# soundMeter.net
KiCad netlist of a schematic drawn in EAGLE
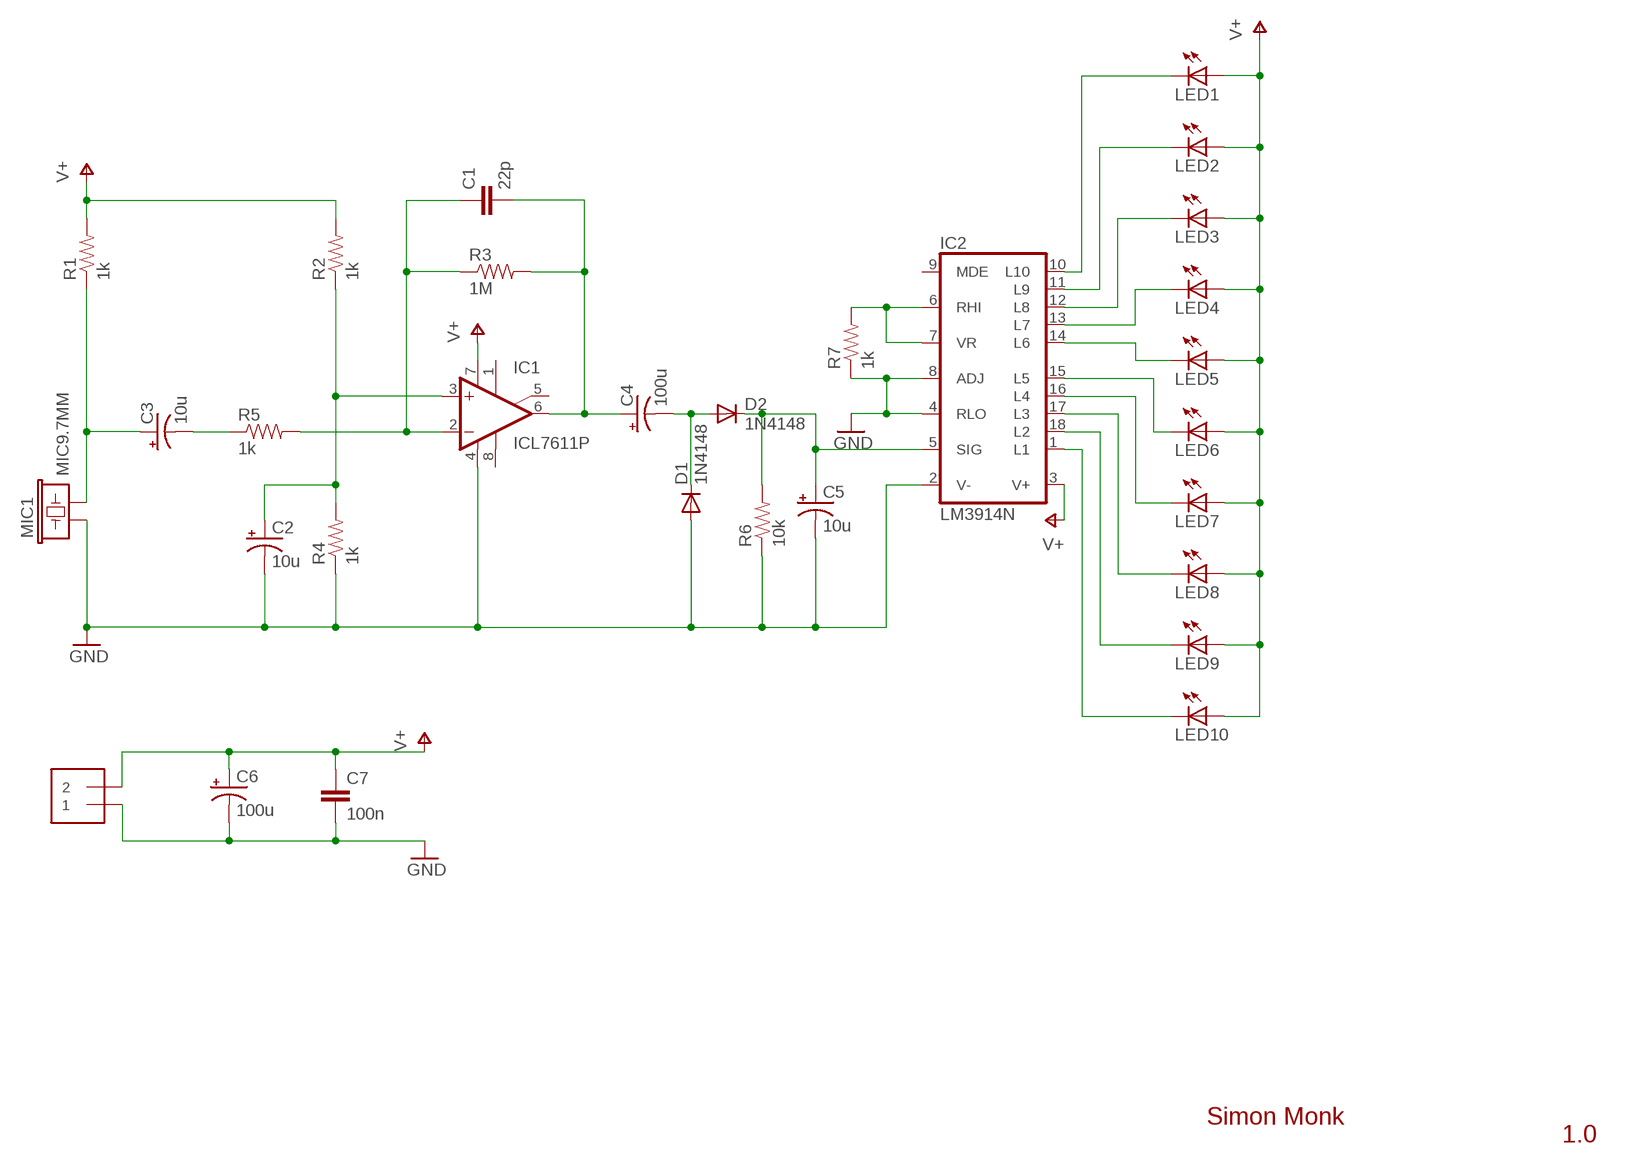
[diagram p0: schematic, sheet 1]

(export (version "E")
  (design (tool "Eeschema 10.0.6"))
  (components
    (comp (ref "C1")
      (value "22p")
      (footprint "eagle-import:CAP-PTH-SMALL")
      (libsource (lib "eagle-import") (part "CAPPTH"))
    )
    (comp (ref "C2")
      (value "10u")
      (footprint "eagle-import:CPOL-RADIAL-10UF-25V")
      (libsource (lib "eagle-import") (part "CAP_POLPTH2"))
    )
    (comp (ref "C3")
      (value "10u")
      (footprint "eagle-import:CPOL-RADIAL-10UF-25V")
      (libsource (lib "eagle-import") (part "CAP_POLPTH2"))
    )
    (comp (ref "C4")
      (value "100u")
      (footprint "eagle-import:CPOL-RADIAL-10UF-25V")
      (libsource (lib "eagle-import") (part "CAP_POLPTH2"))
    )
    (comp (ref "C5")
      (value "10u")
      (footprint "eagle-import:CPOL-RADIAL-10UF-25V")
      (libsource (lib "eagle-import") (part "CAP_POLPTH2"))
    )
    (comp (ref "C6")
      (value "100u")
      (footprint "eagle-import:CPOL-RADIAL-10UF-25V")
      (libsource (lib "eagle-import") (part "CAP_POLPTH2"))
    )
    (comp (ref "C7")
      (value "100n")
      (footprint "eagle-import:CAP-PTH-SMALL")
      (libsource (lib "eagle-import") (part "CAPPTH"))
    )
    (comp (ref "D1")
      (value "1N4148")
      (footprint "eagle-import:DO35-7")
      (libsource (lib "eagle-import") (part "1N4148DO35-7"))
    )
    (comp (ref "D2")
      (value "1N4148")
      (footprint "eagle-import:DO35-7")
      (libsource (lib "eagle-import") (part "1N4148DO35-7"))
    )
    (comp (ref "IC1")
      (value "ICL7611P")
      (footprint "eagle-import:DIL08")
      (libsource (lib "eagle-import") (part "ICL7611P"))
    )
    (comp (ref "IC2")
      (value "LM3914N")
      (footprint "eagle-import:DIL18")
      (libsource (lib "eagle-import") (part "LM3914N"))
    )
    (comp (ref "J1")
      (value "1X2-3.5MM")
      (footprint "eagle-import:1X2-3.5MM")
      (libsource (lib "eagle-import") (part "1X2-3.5MM"))
    )
    (comp (ref "LED1")
      (value "LED3MM")
      (footprint "eagle-import:LED3MM")
      (libsource (lib "eagle-import") (part "LED3MM"))
    )
    (comp (ref "LED2")
      (value "LED3MM")
      (footprint "eagle-import:LED3MM")
      (libsource (lib "eagle-import") (part "LED3MM"))
    )
    (comp (ref "LED3")
      (value "LED3MM")
      (footprint "eagle-import:LED3MM")
      (libsource (lib "eagle-import") (part "LED3MM"))
    )
    (comp (ref "LED4")
      (value "LED3MM")
      (footprint "eagle-import:LED3MM")
      (libsource (lib "eagle-import") (part "LED3MM"))
    )
    (comp (ref "LED5")
      (value "LED3MM")
      (footprint "eagle-import:LED3MM")
      (libsource (lib "eagle-import") (part "LED3MM"))
    )
    (comp (ref "LED6")
      (value "LED3MM")
      (footprint "eagle-import:LED3MM")
      (libsource (lib "eagle-import") (part "LED3MM"))
    )
    (comp (ref "LED7")
      (value "LED3MM")
      (footprint "eagle-import:LED3MM")
      (libsource (lib "eagle-import") (part "LED3MM"))
    )
    (comp (ref "LED8")
      (value "LED3MM")
      (footprint "eagle-import:LED3MM")
      (libsource (lib "eagle-import") (part "LED3MM"))
    )
    (comp (ref "LED9")
      (value "LED3MM")
      (footprint "eagle-import:LED3MM")
      (libsource (lib "eagle-import") (part "LED3MM"))
    )
    (comp (ref "LED10")
      (value "LED3MM")
      (footprint "eagle-import:LED3MM")
      (libsource (lib "eagle-import") (part "LED3MM"))
    )
    (comp (ref "MIC1")
      (value "MIC9.7MM")
      (footprint "eagle-import:MIC-9.7MM")
      (libsource (lib "eagle-import") (part "MIC9.7MM"))
    )
    (comp (ref "R1")
      (value "1k")
      (footprint "eagle-import:AXIAL-0.4")
      (libsource (lib "eagle-import") (part "RESISTORPTH-1/4W"))
    )
    (comp (ref "R2")
      (value "1k")
      (footprint "eagle-import:AXIAL-0.4")
      (libsource (lib "eagle-import") (part "RESISTORPTH-1/4W"))
    )
    (comp (ref "R3")
      (value "1M")
      (footprint "eagle-import:AXIAL-0.4")
      (libsource (lib "eagle-import") (part "RESISTORPTH-1/4W"))
    )
    (comp (ref "R4")
      (value "1k")
      (footprint "eagle-import:AXIAL-0.4")
      (libsource (lib "eagle-import") (part "RESISTORPTH-1/4W"))
    )
    (comp (ref "R5")
      (value "1k")
      (footprint "eagle-import:AXIAL-0.4")
      (libsource (lib "eagle-import") (part "RESISTORPTH-1/4W"))
    )
    (comp (ref "R6")
      (value "10k")
      (footprint "eagle-import:AXIAL-0.4")
      (libsource (lib "eagle-import") (part "RESISTORPTH-1/4W"))
    )
    (comp (ref "R7")
      (value "1k")
      (footprint "eagle-import:AXIAL-0.4")
      (libsource (lib "eagle-import") (part "RESISTORPTH-1/4W"))
    )
  )
  (nets
    (net (code "1") (name "GND") (class "Default")
      (node (ref "C2") (pin "2") (pinfunction "-_2") (pintype "passive"))
      (node (ref "C5") (pin "2") (pinfunction "-_2") (pintype "passive"))
      (node (ref "C6") (pin "2") (pinfunction "-_2") (pintype "passive"))
      (node (ref "C7") (pin "2") (pinfunction "2_2") (pintype "passive"))
      (node (ref "D1") (pin "A") (pinfunction "A_A") (pintype "passive"))
      (node (ref "IC1") (pin "4") (pinfunction "V-_4") (pintype "power_in"))
      (node (ref "IC2") (pin "2") (pinfunction "V-_2") (pintype "power_in"))
      (node (ref "IC2") (pin "4") (pinfunction "RLO_4") (pintype "input"))
      (node (ref "IC2") (pin "8") (pinfunction "ADJ_8") (pintype "input"))
      (node (ref "J1") (pin "1") (pinfunction "1_1") (pintype "passive"))
      (node (ref "MIC1") (pin "1") (pinfunction "1_1") (pintype "passive"))
      (node (ref "R4") (pin "P$1") (pinfunction "1_P$1") (pintype "passive"))
      (node (ref "R6") (pin "P$1") (pinfunction "1_P$1") (pintype "passive"))
      (node (ref "R7") (pin "P$1") (pinfunction "1_P$1") (pintype "passive"))
    )
    (net (code "2") (name "Net-(C2-+)") (class "Default")
      (node (ref "C2") (pin "1") (pinfunction "+_1") (pintype "passive"))
      (node (ref "IC1") (pin "3") (pinfunction "+IN_3") (pintype "input"))
      (node (ref "R2") (pin "P$1") (pinfunction "1_P$1") (pintype "passive"))
      (node (ref "R4") (pin "P$2") (pinfunction "2_P$2") (pintype "passive"))
    )
    (net (code "3") (name "Net-(C3-+)") (class "Default")
      (node (ref "C3") (pin "1") (pinfunction "+_1") (pintype "passive"))
      (node (ref "MIC1") (pin "2") (pinfunction "2_2") (pintype "passive"))
      (node (ref "R1") (pin "P$1") (pinfunction "1_P$1") (pintype "passive"))
    )
    (net (code "4") (name "Net-(C3--)") (class "Default")
      (node (ref "C3") (pin "2") (pinfunction "-_2") (pintype "passive"))
      (node (ref "R5") (pin "P$1") (pinfunction "1_P$1") (pintype "passive"))
    )
    (net (code "5") (name "Net-(C4-+)") (class "Default")
      (node (ref "C1") (pin "2") (pinfunction "2_2") (pintype "passive"))
      (node (ref "C4") (pin "1") (pinfunction "+_1") (pintype "passive"))
      (node (ref "IC1") (pin "6") (pinfunction "OUT_6") (pintype "output"))
      (node (ref "R3") (pin "P$2") (pinfunction "2_P$2") (pintype "passive"))
    )
    (net (code "6") (name "Net-(C4--)") (class "Default")
      (node (ref "C4") (pin "2") (pinfunction "-_2") (pintype "passive"))
      (node (ref "D1") (pin "C") (pinfunction "C_C") (pintype "passive"))
      (node (ref "D2") (pin "A") (pinfunction "A_A") (pintype "passive"))
    )
    (net (code "7") (name "Net-(C5-+)") (class "Default")
      (node (ref "C5") (pin "1") (pinfunction "+_1") (pintype "passive"))
      (node (ref "D2") (pin "C") (pinfunction "C_C") (pintype "passive"))
      (node (ref "IC2") (pin "5") (pinfunction "SIG_5") (pintype "input"))
      (node (ref "R6") (pin "P$2") (pinfunction "2_P$2") (pintype "passive"))
    )
    (net (code "8") (name "Net-(IC1--IN)") (class "Default")
      (node (ref "C1") (pin "1") (pinfunction "1_1") (pintype "passive"))
      (node (ref "IC1") (pin "2") (pinfunction "-IN_2") (pintype "input"))
      (node (ref "R3") (pin "P$1") (pinfunction "1_P$1") (pintype "passive"))
      (node (ref "R5") (pin "P$2") (pinfunction "2_P$2") (pintype "passive"))
    )
    (net (code "9") (name "Net-(IC2-L1)") (class "Default")
      (node (ref "IC2") (pin "1") (pinfunction "L1_1") (pintype "output"))
      (node (ref "LED10") (pin "K") (pinfunction "C_K") (pintype "passive"))
    )
    (net (code "10") (name "Net-(IC2-L2)") (class "Default")
      (node (ref "IC2") (pin "18") (pinfunction "L2_18") (pintype "output"))
      (node (ref "LED9") (pin "K") (pinfunction "C_K") (pintype "passive"))
    )
    (net (code "11") (name "Net-(IC2-L3)") (class "Default")
      (node (ref "IC2") (pin "17") (pinfunction "L3_17") (pintype "output"))
      (node (ref "LED8") (pin "K") (pinfunction "C_K") (pintype "passive"))
    )
    (net (code "12") (name "Net-(IC2-L4)") (class "Default")
      (node (ref "IC2") (pin "16") (pinfunction "L4_16") (pintype "output"))
      (node (ref "LED7") (pin "K") (pinfunction "C_K") (pintype "passive"))
    )
    (net (code "13") (name "Net-(IC2-L5)") (class "Default")
      (node (ref "IC2") (pin "15") (pinfunction "L5_15") (pintype "output"))
      (node (ref "LED6") (pin "K") (pinfunction "C_K") (pintype "passive"))
    )
    (net (code "14") (name "Net-(IC2-L6)") (class "Default")
      (node (ref "IC2") (pin "14") (pinfunction "L6_14") (pintype "output"))
      (node (ref "LED5") (pin "K") (pinfunction "C_K") (pintype "passive"))
    )
    (net (code "15") (name "Net-(IC2-L7)") (class "Default")
      (node (ref "IC2") (pin "13") (pinfunction "L7_13") (pintype "output"))
      (node (ref "LED4") (pin "K") (pinfunction "C_K") (pintype "passive"))
    )
    (net (code "16") (name "Net-(IC2-L8)") (class "Default")
      (node (ref "IC2") (pin "12") (pinfunction "L8_12") (pintype "output"))
      (node (ref "LED3") (pin "K") (pinfunction "C_K") (pintype "passive"))
    )
    (net (code "17") (name "Net-(IC2-L9)") (class "Default")
      (node (ref "IC2") (pin "11") (pinfunction "L9_11") (pintype "output"))
      (node (ref "LED2") (pin "K") (pinfunction "C_K") (pintype "passive"))
    )
    (net (code "18") (name "Net-(IC2-L10)") (class "Default")
      (node (ref "IC2") (pin "10") (pinfunction "L10_10") (pintype "output"))
      (node (ref "LED1") (pin "K") (pinfunction "C_K") (pintype "passive"))
    )
    (net (code "19") (name "Net-(IC2-RHI)") (class "Default")
      (node (ref "IC2") (pin "6") (pinfunction "RHI_6") (pintype "input"))
      (node (ref "IC2") (pin "7") (pinfunction "VR_7") (pintype "output"))
      (node (ref "R7") (pin "P$2") (pinfunction "2_P$2") (pintype "passive"))
    )
    (net (code "20") (name "V+") (class "Default")
      (node (ref "C6") (pin "1") (pinfunction "+_1") (pintype "passive"))
      (node (ref "C7") (pin "1") (pinfunction "1_1") (pintype "passive"))
      (node (ref "IC1") (pin "7") (pinfunction "V+_7") (pintype "power_in"))
      (node (ref "IC2") (pin "3") (pinfunction "V+_3") (pintype "power_in"))
      (node (ref "J1") (pin "2") (pinfunction "2_2") (pintype "passive"))
      (node (ref "LED1") (pin "A") (pinfunction "A_A") (pintype "passive"))
      (node (ref "LED10") (pin "A") (pinfunction "A_A") (pintype "passive"))
      (node (ref "LED2") (pin "A") (pinfunction "A_A") (pintype "passive"))
      (node (ref "LED3") (pin "A") (pinfunction "A_A") (pintype "passive"))
      (node (ref "LED4") (pin "A") (pinfunction "A_A") (pintype "passive"))
      (node (ref "LED5") (pin "A") (pinfunction "A_A") (pintype "passive"))
      (node (ref "LED6") (pin "A") (pinfunction "A_A") (pintype "passive"))
      (node (ref "LED7") (pin "A") (pinfunction "A_A") (pintype "passive"))
      (node (ref "LED8") (pin "A") (pinfunction "A_A") (pintype "passive"))
      (node (ref "LED9") (pin "A") (pinfunction "A_A") (pintype "passive"))
      (node (ref "R1") (pin "P$2") (pinfunction "2_P$2") (pintype "passive"))
      (node (ref "R2") (pin "P$2") (pinfunction "2_P$2") (pintype "passive"))
    )
    (net (code "21") (name "unconnected-(IC1-ON1-Pad1)") (class "Default")
      (node (ref "IC1") (pin "1") (pinfunction "ON1_1") (pintype "passive"))
    )
    (net (code "22") (name "unconnected-(IC1-ON2-Pad5)") (class "Default")
      (node (ref "IC1") (pin "5") (pinfunction "ON2_5") (pintype "passive"))
    )
    (net (code "23") (name "unconnected-(IC1-OPT-Pad8)") (class "Default")
      (node (ref "IC1") (pin "8") (pinfunction "OPT_8") (pintype "passive"))
    )
    (net (code "24") (name "unconnected-(IC2-MDE-Pad9)") (class "Default")
      (node (ref "IC2") (pin "9") (pinfunction "MDE_9") (pintype "input"))
    )
  )
)
